# 24V8A.net
KiCad netlist of a schematic drawn in Altium Designer
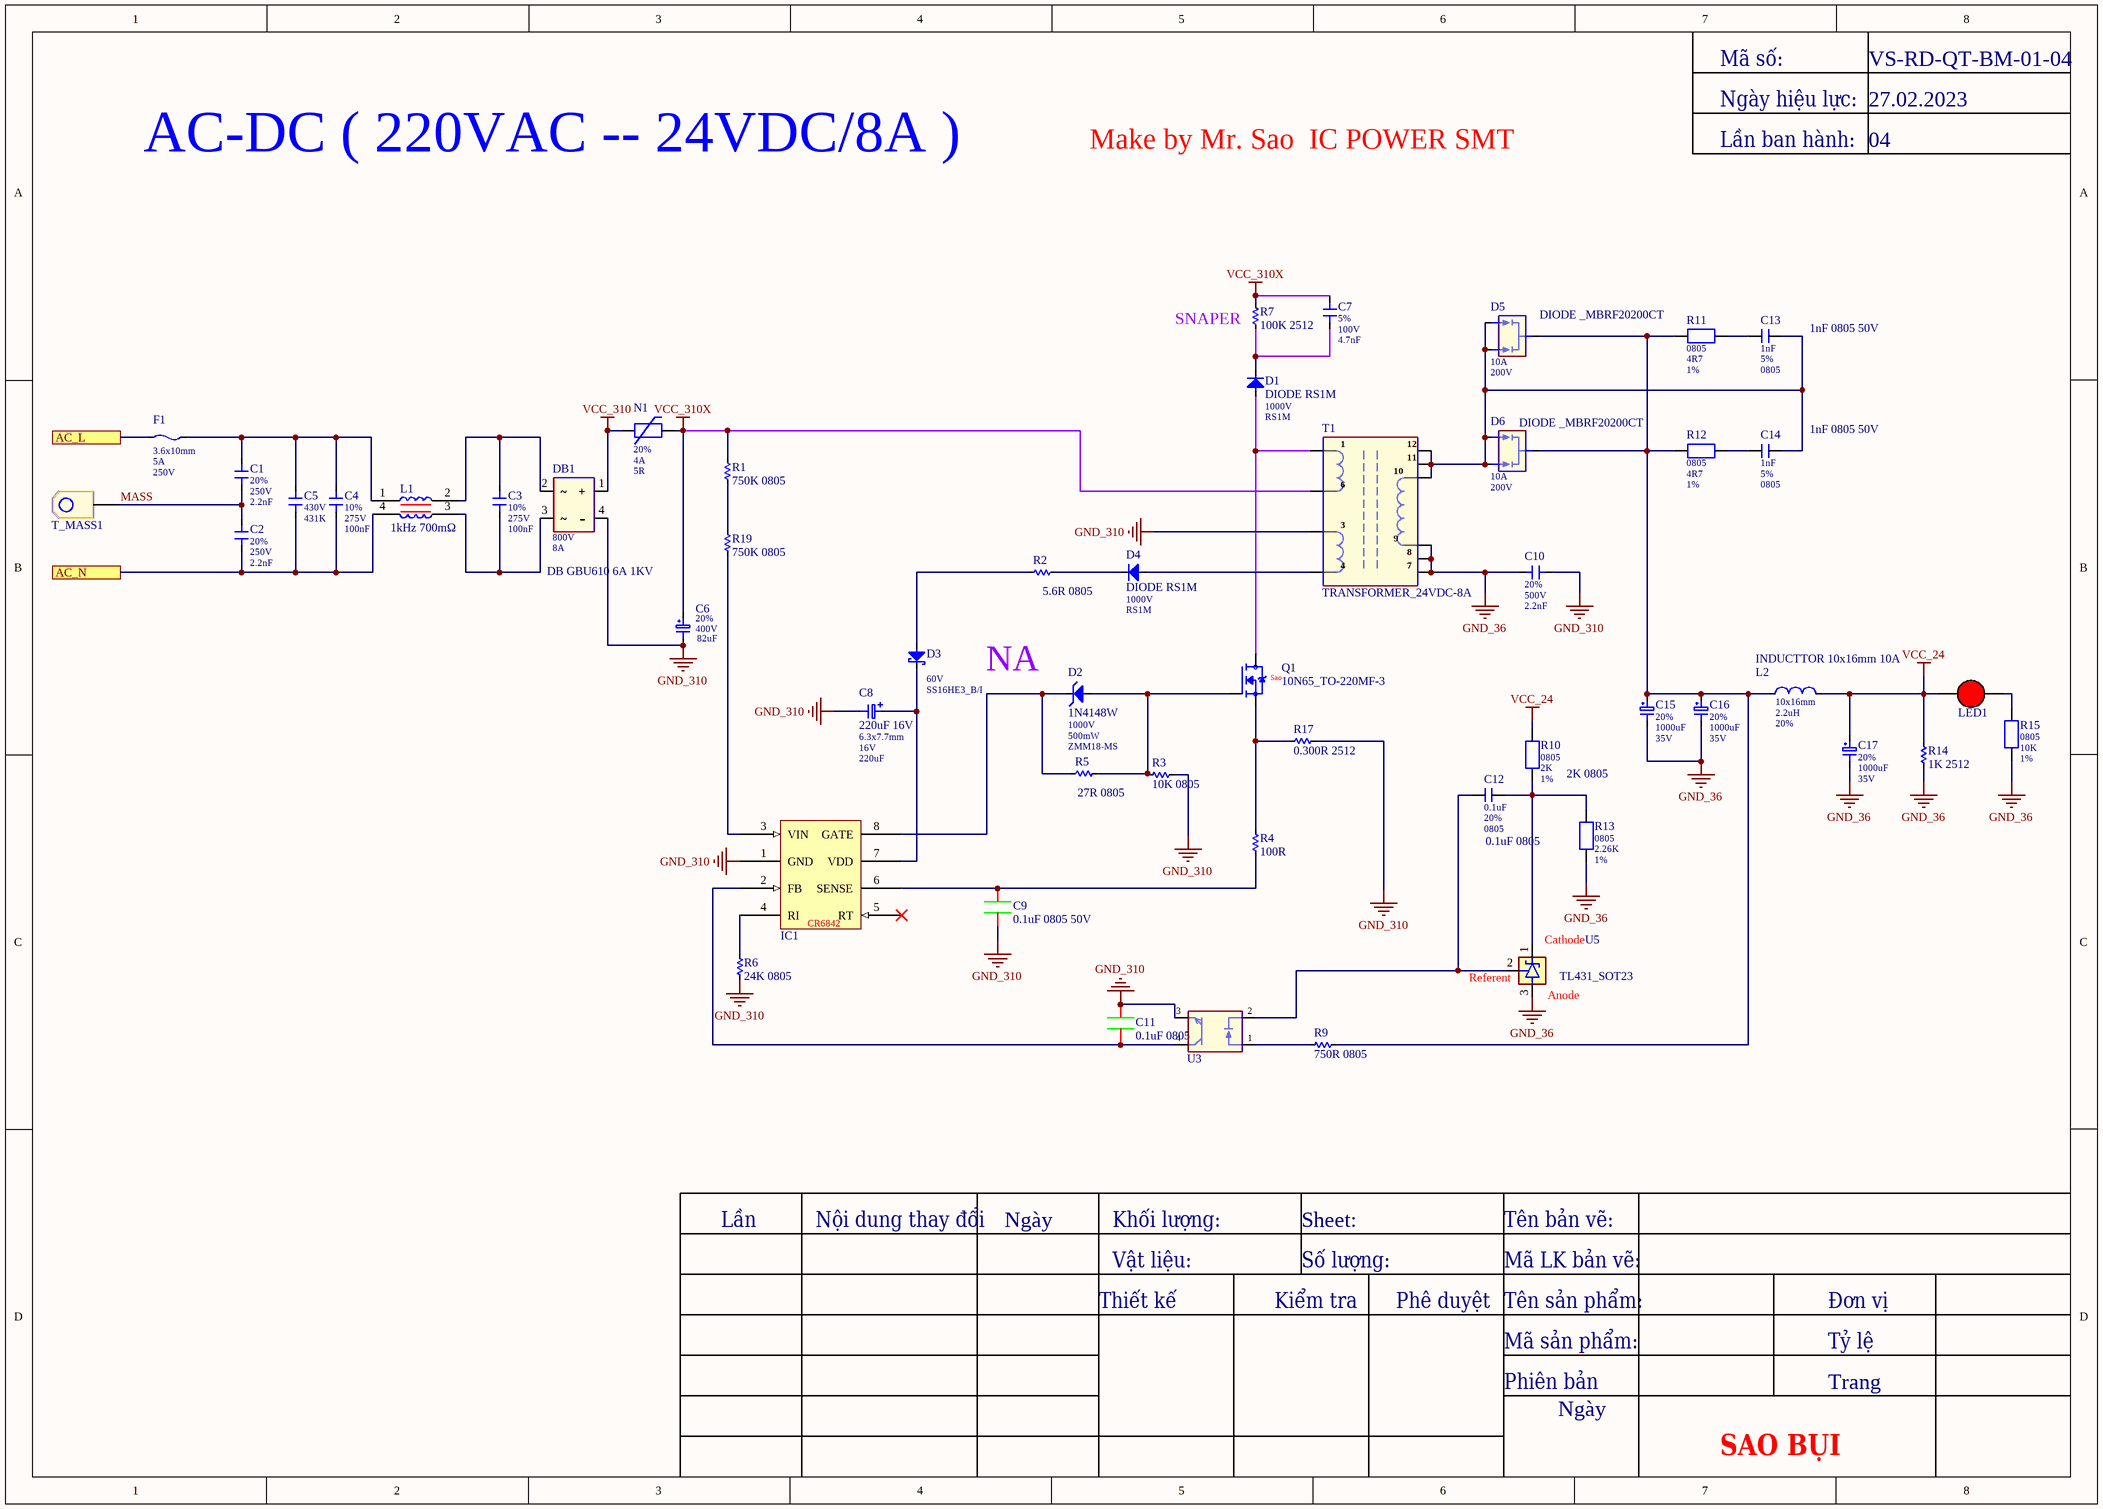
[diagram p0: 24V8A.SchDoc]

(export (version "E")
  (design (tool "Eeschema 10.0.6"))
  (components
    (comp (ref "C1")
      (value "2.2nF 250V")
      (footprint "CAP_CT707BY5V222M250VACB")
      (fields
        (field (name "TOLERANCE") "20%")
        (field (name "VOLTAGE") "250V")
        (field (name "CAPACITANCE") "2.2nF")
      )
      (libsource (lib "Integrated_Library_36V5A") (part "CAP-VAR;TH,2.2nF,20%,P=5mm,250V"))
    )
    (comp (ref "C2")
      (value "2.2nF 250V")
      (footprint "CAP_CT707BY5V222M250VACB")
      (fields
        (field (name "TOLERANCE") "20%")
        (field (name "VOLTAGE") "250V")
        (field (name "CAPACITANCE") "2.2nF")
      )
      (libsource (lib "Integrated_Library_36V5A") (part "CAP-VAR;TH,2.2nF,20%,P=5mm,250V"))
    )
    (comp (ref "C3")
      (value "100nF 275V P=15mm")
      (footprint "CAP-FILM_X2-104K-275VAC")
      (fields
        (field (name "TOLERANCE") "10%")
        (field (name "VOLTAGE") "275V")
        (field (name "CAPACITANCE") "100nF")
      )
      (libsource (lib "Integrated_Library_36V5A") (part "CAP-FILM;TH,100nF,10%,P=15mm,275V"))
    )
    (comp (ref "C4")
      (value "100nF 275V P=15mm")
      (footprint "CAP-FILM_X2-104K-275VAC")
      (fields
        (field (name "TOLERANCE") "10%")
        (field (name "VOLTAGE") "275V")
        (field (name "CAPACITANCE") "100nF")
      )
      (libsource (lib "Integrated_Library_36V5A") (part "CAP-FILM;TH,100nF,10%,P=15mm,275V"))
    )
    (comp (ref "C5")
      (value "10D471")
      (footprint "C_7D431K")
      (fields (field (name "VOLTAGE") "430V") (field (name "CAPACITANCE") "431K"))
      (libsource (lib "Integrated_Library_36V5A") (part "CAP-VAR;TH,07D431K,P=5mm,430V"))
    )
    (comp (ref "C6")
      (value "CAP-ALUM,TH;100uF,20%,18x36mm,450V")
      (footprint "CAP-ALUM_SHC450V100UF01EC3238")
      (fields
        (field (name "TOLERANCE") "20%")
        (field (name "VOLTAGE") "400V")
        (field (name "CAPACITANCE") "82uF")
      )
      (libsource (lib "Integrated_Library_36V5A") (part "CAP-ALUM,TH;100uF,20%,18x36mm,450V"))
    )
    (comp (ref "C7")
      (value "4.7nF 100V")
      (footprint "CAP-MICA_CFA2A472JN0231")
      (fields
        (field (name "TOLERANCE") "5%")
        (field (name "VOLTAGE") "100V")
        (field (name "CAPACITANCE") "4.7nF")
      )
      (libsource (lib "Integrated_Library_36V5A") (part "CAP-MICA;TH,4.7nF,5%,P=4mm,100V"))
    )
    (comp (ref "C8")
      (value "220uF 16V")
      (footprint "C_ALUM_6.3x7.7mm")
      (fields
        (field (name "TOLERANCE") "20%")
        (field (name "PACKAGE") "6.3x7.7mm")
        (field (name "VOLTAGE") "16V")
        (field (name "CAPACITANCE") "220uF")
      )
      (libsource (lib "TMAX13") (part "CMP-002-000004-3"))
    )
    (comp (ref "C9")
      (value "0.1uF 0805 50V")
      (footprint "CN-SMD-0805")
      (libsource (lib "Sao_Bui_BK_HN") (part "CAP_SMD"))
    )
    (comp (ref "C10")
      (value "2.2nF 500V")
      (footprint "C_DE1E3RA222MJ4BQ01F")
      (fields
        (field (name "TOLERANCE") "20%")
        (field (name "VOLTAGE") "500V")
        (field (name "CAPACITANCE") "2.2nF")
      )
      (libsource (lib "Integrated_Library_36V5A") (part "CAP-VAR;TH,2.2nF,20%,P=9mm,500V"))
    )
    (comp (ref "C11")
      (value "0.1uF 0805")
      (footprint "CN-SMD-0805")
      (libsource (lib "Sao_Bui_BK_HN") (part "CAP_SMD"))
    )
    (comp (ref "C12")
      (value "0.1uF 0805")
      (footprint "C_0805_H0.5")
      (fields
        (field (name "VOLTAGE") "50V")
        (field (name "CAPACITANCE") "0.1uF")
        (field (name "TOLERANCE") "20%")
        (field (name "PACKAGE") "0805")
      )
      (libsource (lib "Integrated_Library_36V5A") (part "CAP-CER_SMD_100nF_20%_0805_50V_X7R"))
    )
    (comp (ref "C13")
      (value "1nF 0805 50V")
      (footprint "C_0805_H0.5")
      (fields
        (field (name "VOLTAGE") "50V")
        (field (name "CAPACITANCE") "1nF")
        (field (name "TOLERANCE") "5%")
        (field (name "PACKAGE") "0805")
      )
      (libsource (lib "Integrated_Library_36V5A") (part "CAP-CER_SMD_1nF_5%_0805_50V_X7R"))
    )
    (comp (ref "C14")
      (value "1nF 0805 50V")
      (footprint "C_0805_H0.5")
      (fields
        (field (name "VOLTAGE") "50V")
        (field (name "CAPACITANCE") "1nF")
        (field (name "TOLERANCE") "5%")
        (field (name "PACKAGE") "0805")
      )
      (libsource (lib "Integrated_Library_36V5A") (part "CAP-CER_SMD_1nF_5%_0805_50V_X7R"))
    )
    (comp (ref "C15")
      (value "470uF 50V")
      (footprint "CAP-ALUM_ 50V470uF CD288")
      (fields
        (field (name "TOLERANCE") "20%")
        (field (name "CAPACITANCE") "1000uF")
        (field (name "VOLTAGE") "35V")
      )
      (libsource (lib "Integrated_Library_36V5A") (part "CAP-ALUM,TH;470uF,20%,10x20mm,50V"))
    )
    (comp (ref "C16")
      (value "470uF 50V")
      (footprint "CAP-ALUM_ 50V470uF CD288")
      (fields
        (field (name "TOLERANCE") "20%")
        (field (name "CAPACITANCE") "1000uF")
        (field (name "VOLTAGE") "35V")
      )
      (libsource (lib "Integrated_Library_36V5A") (part "CAP-ALUM,TH;470uF,20%,10x20mm,50V"))
    )
    (comp (ref "C17")
      (value "470uF 50V")
      (footprint "CAP-ALUM_ 50V470uF CD288")
      (fields
        (field (name "TOLERANCE") "20%")
        (field (name "CAPACITANCE") "1000uF")
        (field (name "VOLTAGE") "35V")
      )
      (libsource (lib "Integrated_Library_36V5A") (part "CAP-ALUM,TH;470uF,20%,10x20mm,50V"))
    )
    (comp (ref "D1")
      (value "DIODE RS1M")
      (footprint "DO-214AC")
      (fields (field (name "VOLTAGE") "1000V") (field (name "MANUFACTURE PART NUMBER 1") "RS1M"))
      (libsource (lib "VSHOME Vault") (part "DIODE-RECTIFIER_{lt}Manufacture Part Number 1{gt}"))
    )
    (comp (ref "D2")
      (value "1N4148W")
      (footprint "SOD-80")
      (description "Diode_SMD, 1N4148W, T4   SOD123\n- 100V 400mW 1.25V@150mA 8ns 150mA SOD-123 Switching Diode ROHS")
      (fields
        (field (name "VOLTAGE") "1000V")
        (field (name "POWER") "500mW")
        (field (name "MANUFACTURE PART NUMBER 1") "ZMM18-MS")
      )
      (libsource (lib "VSHOME Vault") (part "DIODE-ZENER_{lt}Manufacture Part Number 1{gt}"))
    )
    (comp (ref "D3")
      (value "DIODE_FR107 ( F7 )")
      (footprint "DIODE-SCHOTTKY_SS34B")
      (fields (field (name "VOLTAGE") "60V") (field (name "MANUFACTURE PART NUMBER 1") "SS16HE3_B/I"))
      (libsource (lib "VSHOME Vault") (part "DIODE-SCHOTTKY_{lt}Manufacture Part Number 1{gt}"))
    )
    (comp (ref "D4")
      (value "DIODE RS1M")
      (footprint "DO-214AC")
      (fields (field (name "VOLTAGE") "1000V") (field (name "MANUFACTURE PART NUMBER 1") "RS1M"))
      (libsource (lib "VSHOME Vault") (part "DIODE-RECTIFIER_{lt}Manufacture Part Number 1{gt}"))
    )
    (comp (ref "D5")
      (value "DIODE _MBRF20200CT")
      (footprint "TO220H2")
      (fields (field (name "POWER") "10A") (field (name "VOLTAGE") "200V"))
      (libsource (lib "Integrated_Library_36V5A") (part "DIODE-SCHOTTKY;200V,10A,TO-220,MBRF20200CT"))
    )
    (comp (ref "D6")
      (value "DIODE _MBRF20200CT")
      (footprint "TO220H2")
      (fields (field (name "POWER") "10A") (field (name "VOLTAGE") "200V"))
      (libsource (lib "Integrated_Library_36V5A") (part "DIODE-SCHOTTKY;200V,10A,TO-220,MBRF20200CT"))
    )
    (comp (ref "DB1")
      (value "DB GBU610 6A 1KV")
      (footprint "DIODE-DRIDGE_KBL608")
      (fields (field (name "VOLTAGE") "800V") (field (name "POWER") "8A"))
      (libsource (lib "Integrated_Library_36V5A") (part "DIODE-BRIDGE_KBL608"))
    )
    (comp (ref "F1")
      (value "FUSE 5A 250V")
      (footprint "FUSE_0674.500DRT4")
      (fields (field (name "PACKAGE") "3.6x10mm") (field (name "POWER") "5A") (field (name "VOLTAGE") "250V"))
      (libsource (lib "Integrated_Library_36V5A") (part "FUSE;CERAMIC,5A,250V,3.6x10mm,0674.500DRT4"))
    )
    (comp (ref "IC1")
      (value "CR6842")
      (footprint "SOP8")
      (description "IC_POWER; AC/DC; SOP8; CR6842")
      (fields (field (name "MANUFACTURER") "Chip-Rail"))
      (libsource (lib "Sao_Bui_BK_HN") (part "IC_POWER; AC/DC; SOP8; CR6842S"))
    )
    (comp (ref "L1")
      (value "1kHz 700mΩ")
      (footprint "UU9.8-5mH")
      (description "MODE_CHOKE_DIP, 5mH , 4PIN, UU9.8-5mH, 1kHz 700mΩ")
      (fields
        (field (name "MANUFACTURER PART NUMBER") "UU9.8-5mH")
        (field (name "MANUFACTURER") "FH (Guangdong Fenghua Advanced Tech)")
      )
      (libsource (lib "COMON_MODE_CHOKE") (part "MODE_CHOKE_DIP, 5mH , 4PIN, UU9.8-5mH"))
    )
    (comp (ref "L2")
      (value "INDUCTTOR 10x16mm 10A")
      (footprint "IND_ AIUR-03-2R2M")
      (fields
        (field (name "PACKAGE") "10x16mm")
        (field (name "INDUCTANCE") "2.2uH")
        (field (name "TOLERANCE") "20%")
      )
      (libsource (lib "Integrated_Library_36V5A") (part "IND;2.2uH,20%,9x12mm,3.2A,21mR"))
    )
    (comp (ref "LED1")
      (value "LED;2V,20mA,0805,RED,LSM0805412V")
      (footprint "LED-1206-Red")
      (fields (field (name "VOLTAGE") "2V"))
      (libsource (lib "Integrated_Library_36V5A") (part "LED;2V,20mA,0805,RED,LSM0805412V"))
    )
    (comp (ref "N1")
      (value "THERMISTOR_SCN5D-11")
      (footprint "THERMISTOR_SCN5D-11")
      (description "THERMISTOR_SCN5D-11\r\n- Partnumber:  VDR Varistor\r\n- MPN:  VDR Varistor")
      (fields (field (name "TOLERANCE") "20%") (field (name "POWER") "4A") (field (name "RESISTANCE") "5R"))
      (libsource (lib "Integrated_Library_36V5A") (part "THERMISTOR_SCN5D-11"))
    )
    (comp (ref "Q1")
      (value "10N65_TO-220MF-3")
      (footprint "TO220H2")
      (fields (field (name "MF") "Infineon Technologies") (field (name "MP") "IRF540NSTRLPBF"))
      (libsource (lib "Sao_Bui_BK_HN") (part "FCD9N60NTM"))
    )
    (comp (ref "R1")
      (value "750K 0805")
      (footprint "RES-SMD-0805")
      (fields
        (field (name "MANUFACTURER") "Generic Components")
        (field (name "PUBLISHER") "Altium Hobart Technology Centre")
      )
      (libsource (lib "LIBRARY1") (part "Res-SMD"))
    )
    (comp (ref "R2")
      (value "5.6R 0805")
      (footprint "RES-SMD-0805")
      (fields
        (field (name "MANUFACTURER") "Generic Components")
        (field (name "PUBLISHER") "Altium Hobart Technology Centre")
      )
      (libsource (lib "LIBRARY1") (part "Res-SMD"))
    )
    (comp (ref "R3")
      (value "10K 0805")
      (footprint "RES-SMD-0805")
      (fields
        (field (name "MANUFACTURER") "Generic Components")
        (field (name "PUBLISHER") "Altium Hobart Technology Centre")
      )
      (libsource (lib "LIBRARY1") (part "Res-SMD"))
    )
    (comp (ref "R4")
      (value "100R")
      (footprint "RES-SMD-0805")
      (description "RES_SMD, 1K , 1%, 0805\r\n- Partnumber: CHP0805AFX-1001ELF\r\n- MPN: Bourns")
      (fields
        (field (name "MANUFACTURER") "Generic Components")
        (field (name "PUBLISHER") "Altium Hobart Technology Centre")
      )
      (libsource (lib "LIBRARY1") (part "Res-SMD"))
    )
    (comp (ref "R5")
      (value "27R 0805")
      (footprint "RES-SMD-0805")
      (fields
        (field (name "MANUFACTURER") "Generic Components")
        (field (name "PUBLISHER") "Altium Hobart Technology Centre")
      )
      (libsource (lib "LIBRARY1") (part "Res-SMD"))
    )
    (comp (ref "R6")
      (value "24K 0805")
      (footprint "RES-SMD-0805")
      (fields
        (field (name "MANUFACTURER") "Generic Components")
        (field (name "PUBLISHER") "Altium Hobart Technology Centre")
      )
      (libsource (lib "LIBRARY1") (part "Res-SMD"))
    )
    (comp (ref "R7")
      (value "100K 2512")
      (footprint "RES-SMD-2512")
      (fields
        (field (name "MANUFACTURER") "Generic Components")
        (field (name "PUBLISHER") "Altium Hobart Technology Centre")
      )
      (libsource (lib "LIBRARY1") (part "Res-SMD"))
    )
    (comp (ref "R9")
      (value "750R 0805")
      (footprint "RES-SMD-0805")
      (fields
        (field (name "MANUFACTURER") "Generic Components")
        (field (name "PUBLISHER") "Altium Hobart Technology Centre")
      )
      (libsource (lib "LIBRARY1") (part "Res-SMD"))
    )
    (comp (ref "R10")
      (value "2K 0805")
      (footprint "R_0805_H0.5")
      (fields
        (field (name "POWER") "1/8W")
        (field (name "PACKAGE") "0805")
        (field (name "RESISTANCE") "2K")
        (field (name "TOLERANCE") "1%")
      )
      (libsource (lib "Integrated_Library_36V5A") (part "RES-SMD;2K,1%,0805,1/8W"))
    )
    (comp (ref "R11")
      (value "4.7R 0805")
      (footprint "R_0805_H0.5")
      (fields
        (field (name "POWER") "1/8W")
        (field (name "PACKAGE") "0805")
        (field (name "RESISTANCE") "4R7")
        (field (name "TOLERANCE") "1%")
      )
      (libsource (lib "Integrated_Library_36V5A") (part "RES-SMD;5R6,1%,0805,1/8W"))
    )
    (comp (ref "R12")
      (value "4.7R 0805")
      (footprint "R_0805_H0.5")
      (fields
        (field (name "POWER") "1/8W")
        (field (name "PACKAGE") "0805")
        (field (name "RESISTANCE") "4R7")
        (field (name "TOLERANCE") "1%")
      )
      (libsource (lib "Integrated_Library_36V5A") (part "RES-SMD;5R6,1%,0805,1/8W"))
    )
    (comp (ref "R13")
      (value "2.26K 0805")
      (footprint "R_0805_H0.5")
      (fields
        (field (name "POWER") "1/8W")
        (field (name "PACKAGE") "0805")
        (field (name "RESISTANCE") "2.26K")
        (field (name "TOLERANCE") "1%")
      )
      (libsource (lib "Integrated_Library_36V5A") (part "RES-SMD;1.5K,1%,0805,1/8W"))
    )
    (comp (ref "R14")
      (value "1K 2512")
      (footprint "RES-SMD-2512")
      (fields
        (field (name "MANUFACTURER") "Generic Components")
        (field (name "PUBLISHER") "Altium Hobart Technology Centre")
      )
      (libsource (lib "LIBRARY1") (part "Res-SMD"))
    )
    (comp (ref "R15")
      (value "10K 0805")
      (footprint "RES_SMD_0805")
      (fields
        (field (name "POWER") "1/8W")
        (field (name "PACKAGE") "0805")
        (field (name "RESISTANCE") "10K")
        (field (name "TOLERANCE") "1%")
      )
      (libsource (lib "NEW_Library") (part "RES-SMD;10K,1%,0805,1/8W"))
    )
    (comp (ref "R17")
      (value "0.300R 2512")
      (footprint "RES-SMD-2512")
      (fields
        (field (name "MANUFACTURER") "Generic Components")
        (field (name "PUBLISHER") "Altium Hobart Technology Centre")
      )
      (libsource (lib "LIBRARY1") (part "Res-SMD"))
    )
    (comp (ref "R19")
      (value "750K 0805")
      (footprint "RES-SMD-0805")
      (fields
        (field (name "MANUFACTURER") "Generic Components")
        (field (name "PUBLISHER") "Altium Hobart Technology Centre")
      )
      (libsource (lib "LIBRARY1") (part "Res-SMD"))
    )
    (comp (ref "T1")
      (value "TRANSFORMER_24VDC-8A")
      (footprint "TRANSFORMER_24V-8A")
      (description "TRANSFORMER_24VDC-8A, Mẫu biến áp dùng cho 24VDC-8A")
      (libsource (lib "TRANSFORMER_DIP") (part "TRANSFORMER_24VDC-8A"))
    )
    (comp (ref "T_MASS1")
      (value "TERMINAL_63824-5")
      (footprint "TERMINAL_63824-5")
      (description "TERMINAL_63824-5\r\n- Partnumber: 63824-5\r\n- MPN: TE Connectivity")
      (libsource (lib "Integrated_Library_36V5A") (part "TERMINAL_63824-5"))
    )
    (comp (ref "U3")
      (value "PC817B")
      (footprint "PC817_DIP")
      (libsource (lib "Integrated_Library_36V5A") (part "OPTO-TH;PC817B"))
    )
    (comp (ref "U5")
      (value "TL431_SOT23")
      (footprint "TL431_SOT23")
      (description "- Partnumber: TL431LIBEDBZRQ1\r\n- MPN: Texas Instruments")
      (libsource (lib "Sao_Bui_BK_HN") (part "TL431"))
    )
  )
  (nets
    (net (code "1") (name "/AC_L") (class "Default")
      (node (ref "F1") (pin "1") (pinfunction "1_1") (pintype "passive"))
    )
    (net (code "2") (name "/AC_N") (class "Default")
      (node (ref "C2") (pin "2") (pinfunction "2_2") (pintype "power_in"))
      (node (ref "C4") (pin "1") (pinfunction "1_1") (pintype "power_in"))
      (node (ref "C5") (pin "2") (pinfunction "2_2") (pintype "power_in"))
      (node (ref "L1") (pin "4") (pinfunction "4_4") (pintype "passive"))
    )
    (net (code "3") (name "/MASS") (class "Default")
      (node (ref "C1") (pin "2") (pinfunction "2_2") (pintype "power_in"))
      (node (ref "C2") (pin "1") (pinfunction "1_1") (pintype "power_in"))
      (node (ref "T_MASS1") (pin "1") (pinfunction "1_1") (pintype "passive"))
    )
    (net (code "4") (name "GND_36") (class "Default")
      (node (ref "C10") (pin "2") (pinfunction "2_2") (pintype "power_in"))
      (node (ref "C15") (pin "1") (pinfunction "1_1") (pintype "power_in"))
      (node (ref "C16") (pin "1") (pinfunction "1_1") (pintype "power_in"))
      (node (ref "C17") (pin "1") (pinfunction "1_1") (pintype "power_in"))
      (node (ref "R13") (pin "2") (pinfunction "2_2") (pintype "power_in"))
      (node (ref "R14") (pin "2") (pinfunction "2_2") (pintype "passive"))
      (node (ref "R15") (pin "1") (pinfunction "1_1") (pintype "power_in"))
      (node (ref "T1") (pin "7") (pinfunction "5_7") (pintype "passive"))
      (node (ref "T1") (pin "8") (pinfunction "6_8") (pintype "passive"))
      (node (ref "T1") (pin "9") (pinfunction "7_9") (pintype "passive"))
      (node (ref "U5") (pin "3") (pinfunction "ANODE_3") (pintype "passive"))
    )
    (net (code "5") (name "GND_310") (class "Default")
      (node (ref "C10") (pin "1") (pinfunction "1_1") (pintype "power_in"))
      (node (ref "C11") (pin "2") (pinfunction "2_2") (pintype "passive"))
      (node (ref "C6") (pin "1") (pinfunction "1_1") (pintype "power_in"))
      (node (ref "C8") (pin "N") (pinfunction "N_N") (pintype "passive"))
      (node (ref "C9") (pin "1") (pinfunction "2_1") (pintype "passive"))
      (node (ref "DB1") (pin "4") (pinfunction "-_4") (pintype "passive"))
      (node (ref "IC1") (pin "1") (pinfunction "GND_1") (pintype "power_in"))
      (node (ref "R17") (pin "1") (pinfunction "1_1") (pintype "passive"))
      (node (ref "R3") (pin "1") (pinfunction "1_1") (pintype "passive"))
      (node (ref "R6") (pin "2") (pinfunction "2_2") (pintype "passive"))
      (node (ref "T1") (pin "3") (pinfunction "3_3") (pintype "passive"))
      (node (ref "U3") (pin "3") (pinfunction "3_3") (pintype "power_in"))
    )
    (net (code "6") (name "Net-(C1-Pad1)") (class "Default")
      (node (ref "C1") (pin "1") (pinfunction "1_1") (pintype "power_in"))
      (node (ref "C4") (pin "2") (pinfunction "2_2") (pintype "power_in"))
      (node (ref "C5") (pin "1") (pinfunction "1_1") (pintype "power_in"))
      (node (ref "F1") (pin "2") (pinfunction "2_2") (pintype "passive"))
      (node (ref "L1") (pin "1") (pinfunction "1_1") (pintype "passive"))
    )
    (net (code "7") (name "Net-(C3-Pad1)") (class "Default")
      (node (ref "C3") (pin "1") (pinfunction "1_1") (pintype "power_in"))
      (node (ref "DB1") (pin "3") (pinfunction "~_3") (pintype "passive"))
      (node (ref "L1") (pin "3") (pinfunction "3_3") (pintype "passive"))
    )
    (net (code "8") (name "Net-(C3-Pad2)") (class "Default")
      (node (ref "C3") (pin "2") (pinfunction "2_2") (pintype "power_in"))
      (node (ref "DB1") (pin "2") (pinfunction "~_2") (pintype "passive"))
      (node (ref "L1") (pin "2") (pinfunction "2_2") (pintype "passive"))
    )
    (net (code "9") (name "Net-(C7-Pad2)") (class "Default")
      (node (ref "C7") (pin "2") (pinfunction "2_2") (pintype "power_in"))
      (node (ref "D1") (pin "K") (pinfunction "K_K") (pintype "passive"))
      (node (ref "R7") (pin "1") (pinfunction "1_1") (pintype "passive"))
    )
    (net (code "10") (name "Net-(C13-Pad2)") (class "Default")
      (node (ref "C13") (pin "2") (pinfunction "2_2") (pintype "power_in"))
      (node (ref "R11") (pin "2") (pinfunction "2_2") (pintype "power_in"))
    )
    (net (code "11") (name "Net-(C14-Pad2)") (class "Default")
      (node (ref "C14") (pin "2") (pinfunction "2_2") (pintype "power_in"))
      (node (ref "R12") (pin "2") (pinfunction "2_2") (pintype "power_in"))
    )
    (net (code "12") (name "Net-(D3-PadA)") (class "Default")
      (node (ref "D3") (pin "A") (pinfunction "A_A") (pintype "passive"))
      (node (ref "R2") (pin "2") (pinfunction "2_2") (pintype "passive"))
    )
    (net (code "13") (name "Net-(D4-PadA)") (class "Default")
      (node (ref "D4") (pin "A") (pinfunction "A_A") (pintype "passive"))
      (node (ref "T1") (pin "4") (pinfunction "4_4") (pintype "passive"))
    )
    (net (code "14") (name "Net-(D4-PadK)") (class "Default")
      (node (ref "D4") (pin "K") (pinfunction "K_K") (pintype "passive"))
      (node (ref "R2") (pin "1") (pinfunction "1_1") (pintype "passive"))
    )
    (net (code "15") (name "Net-(D5-K)") (class "Default")
      (node (ref "C15") (pin "2") (pinfunction "2_2") (pintype "power_in"))
      (node (ref "C16") (pin "2") (pinfunction "2_2") (pintype "power_in"))
      (node (ref "D5") (pin "2") (pinfunction "K_2") (pintype "passive"))
      (node (ref "D6") (pin "2") (pinfunction "K_2") (pintype "passive"))
      (node (ref "L2") (pin "1") (pinfunction "1_1") (pintype "passive"))
      (node (ref "R11") (pin "1") (pinfunction "1_1") (pintype "power_in"))
      (node (ref "R12") (pin "1") (pinfunction "1_1") (pintype "power_in"))
      (node (ref "R9") (pin "1") (pinfunction "1_1") (pintype "passive"))
    )
    (net (code "16") (name "Net-(IC1-FB)") (class "Default")
      (node (ref "C11") (pin "1") (pinfunction "2_1") (pintype "passive"))
      (node (ref "IC1") (pin "2") (pinfunction "FB_2") (pintype "input"))
      (node (ref "U3") (pin "4") (pinfunction "4_4") (pintype "power_in"))
    )
    (net (code "17") (name "Net-(IC1-GATE)") (class "Default")
      (node (ref "D2") (pin "K") (pinfunction "K_K") (pintype "passive"))
      (node (ref "IC1") (pin "8") (pinfunction "GATE_8") (pintype "passive"))
      (node (ref "R5") (pin "2") (pinfunction "2_2") (pintype "passive"))
    )
    (net (code "18") (name "Net-(IC1-RI)") (class "Default")
      (node (ref "IC1") (pin "4") (pinfunction "RI_4") (pintype "passive"))
      (node (ref "R6") (pin "1") (pinfunction "1_1") (pintype "passive"))
    )
    (net (code "19") (name "Net-(IC1-SENSE)") (class "Default")
      (node (ref "C9") (pin "2") (pinfunction "2_2") (pintype "passive"))
      (node (ref "IC1") (pin "6") (pinfunction "SENSE_6") (pintype "passive"))
      (node (ref "R4") (pin "2") (pinfunction "2_2") (pintype "passive"))
    )
    (net (code "20") (name "Net-(IC1-VDD)") (class "Default")
      (node (ref "C8") (pin "P") (pinfunction "P_P") (pintype "passive"))
      (node (ref "D3") (pin "K") (pinfunction "K_K") (pintype "passive"))
      (node (ref "IC1") (pin "7") (pinfunction "VDD_7") (pintype "power_in"))
    )
    (net (code "21") (name "Net-(IC1-VIN)") (class "Default")
      (node (ref "IC1") (pin "3") (pinfunction "VIN_3") (pintype "input"))
      (node (ref "R19") (pin "2") (pinfunction "2_2") (pintype "passive"))
    )
    (net (code "22") (name "Net-(LED1-K)") (class "Default")
      (node (ref "LED1") (pin "2") (pinfunction "K_2") (pintype "passive"))
      (node (ref "R15") (pin "2") (pinfunction "2_2") (pintype "power_in"))
    )
    (net (code "23") (name "Net-(Q1-D)") (class "Default")
      (node (ref "D1") (pin "A") (pinfunction "A_A") (pintype "passive"))
      (node (ref "Q1") (pin "2") (pinfunction "D_2") (pintype "passive"))
      (node (ref "T1") (pin "1") (pinfunction "1_1") (pintype "passive"))
    )
    (net (code "24") (name "Net-(Q1-G)") (class "Default")
      (node (ref "D2") (pin "A") (pinfunction "A_A") (pintype "passive"))
      (node (ref "Q1") (pin "1") (pinfunction "G_1") (pintype "passive"))
      (node (ref "R3") (pin "2") (pinfunction "2_2") (pintype "passive"))
      (node (ref "R5") (pin "1") (pinfunction "1_1") (pintype "passive"))
    )
    (net (code "25") (name "Net-(Q1-S)") (class "Default")
      (node (ref "Q1") (pin "3") (pinfunction "S_3") (pintype "passive"))
      (node (ref "R17") (pin "2") (pinfunction "2_2") (pintype "passive"))
      (node (ref "R4") (pin "1") (pinfunction "1_1") (pintype "passive"))
    )
    (net (code "26") (name "Net-(R1-Pad2)") (class "Default")
      (node (ref "R1") (pin "2") (pinfunction "2_2") (pintype "passive"))
      (node (ref "R19") (pin "1") (pinfunction "1_1") (pintype "passive"))
    )
    (net (code "27") (name "Net-(R9-Pad2)") (class "Default")
      (node (ref "R9") (pin "2") (pinfunction "2_2") (pintype "passive"))
      (node (ref "U3") (pin "1") (pinfunction "1_1") (pintype "power_in"))
    )
    (net (code "28") (name "Net-(T1-10)") (class "Default")
      (node (ref "C13") (pin "1") (pinfunction "1_1") (pintype "power_in"))
      (node (ref "C14") (pin "1") (pinfunction "1_1") (pintype "power_in"))
      (node (ref "D5") (pin "1") (pinfunction "A_1") (pintype "passive"))
      (node (ref "D5") (pin "3") (pinfunction "A_3") (pintype "passive"))
      (node (ref "D6") (pin "1") (pinfunction "A_1") (pintype "passive"))
      (node (ref "D6") (pin "3") (pinfunction "A_3") (pintype "passive"))
      (node (ref "T1") (pin "10") (pinfunction "8_10") (pintype "passive"))
      (node (ref "T1") (pin "11") (pinfunction "9_11") (pintype "passive"))
      (node (ref "T1") (pin "12") (pinfunction "10_12") (pintype "passive"))
    )
    (net (code "29") (name "Net-(U5-CATHODE)") (class "Default")
      (node (ref "C12") (pin "1") (pinfunction "1_1") (pintype "power_in"))
      (node (ref "R10") (pin "2") (pinfunction "2_2") (pintype "power_in"))
      (node (ref "R13") (pin "1") (pinfunction "1_1") (pintype "power_in"))
      (node (ref "U5") (pin "1") (pinfunction "CATHODE_1") (pintype "passive"))
    )
    (net (code "30") (name "Net-(U5-REF)") (class "Default")
      (node (ref "C12") (pin "2") (pinfunction "2_2") (pintype "power_in"))
      (node (ref "U3") (pin "2") (pinfunction "2_2") (pintype "power_in"))
      (node (ref "U5") (pin "2") (pinfunction "REF_2") (pintype "passive"))
    )
    (net (code "31") (name "VCC_24") (class "Default")
      (node (ref "C17") (pin "2") (pinfunction "2_2") (pintype "power_in"))
      (node (ref "L2") (pin "2") (pinfunction "2_2") (pintype "passive"))
      (node (ref "LED1") (pin "1") (pinfunction "A_1") (pintype "passive"))
      (node (ref "R10") (pin "1") (pinfunction "1_1") (pintype "power_in"))
      (node (ref "R14") (pin "1") (pinfunction "1_1") (pintype "passive"))
    )
    (net (code "32") (name "VCC_310") (class "Default")
      (node (ref "DB1") (pin "1") (pinfunction "+_1") (pintype "passive"))
      (node (ref "N1") (pin "1") (pinfunction "1_1") (pintype "passive"))
    )
    (net (code "33") (name "VCC_310X") (class "Default")
      (node (ref "C6") (pin "2") (pinfunction "2_2") (pintype "power_in"))
      (node (ref "C7") (pin "1") (pinfunction "1_1") (pintype "power_in"))
      (node (ref "N1") (pin "2") (pinfunction "2_2") (pintype "passive"))
      (node (ref "R1") (pin "1") (pinfunction "1_1") (pintype "passive"))
      (node (ref "R7") (pin "2") (pinfunction "2_2") (pintype "passive"))
      (node (ref "T1") (pin "6") (pinfunction "6_6") (pintype "passive"))
    )
    (net (code "34") (name "unconnected-(IC1-RT-Pad5)") (class "Default")
      (node (ref "IC1") (pin "5") (pinfunction "RT_5") (pintype "input+no_connect"))
    )
  )
)
